# Sheet1.net
KiCad netlist of a schematic drawn in Altium Designer
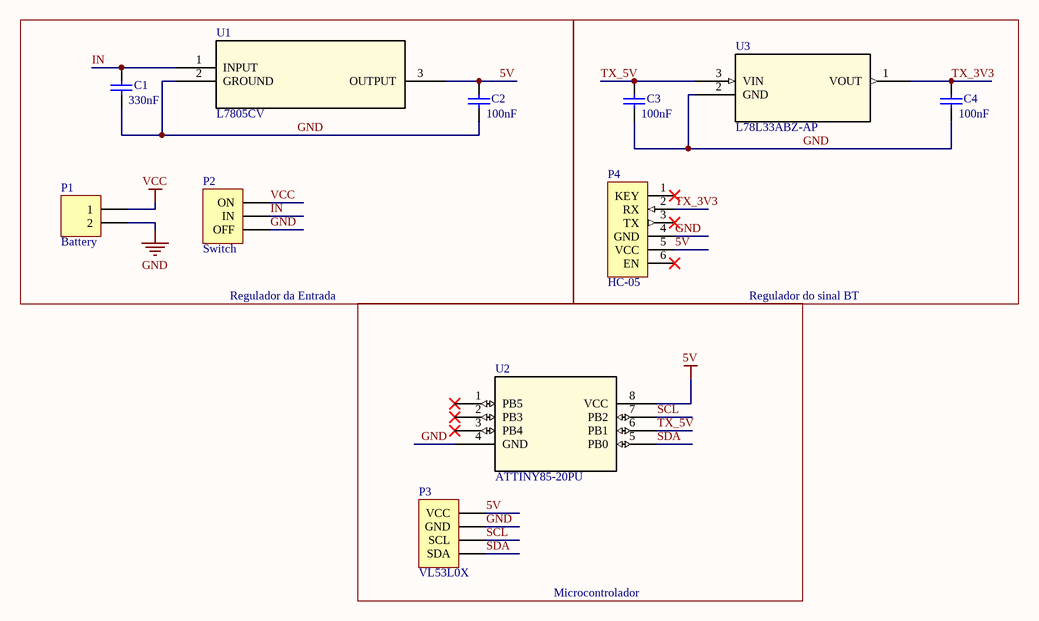
[diagram p0: Sheet1.SchDoc]

(export (version "E")
  (design (tool "Eeschema 10.0.6"))
  (components
    (comp (ref "C1")
      (value "330nF")
      (footprint "RAD-0.3")
      (description "Capacitor")
      (fields (field (name "Comment") "Cap") (field (name "PUBLISHER") "Altium Limited"))
      (libsource (lib "Miscellaneous Devices") (part "Cap"))
    )
    (comp (ref "C2")
      (value "100nF")
      (footprint "RAD-0.3")
      (description "Capacitor")
      (fields (field (name "Comment") "Cap") (field (name "PUBLISHER") "Altium Limited"))
      (libsource (lib "Miscellaneous Devices") (part "Cap"))
    )
    (comp (ref "C3")
      (value "100nF")
      (footprint "RAD-0.2")
      (description "Capacitor")
      (libsource (lib "Basic Library") (part "C"))
    )
    (comp (ref "C4")
      (value "100nF")
      (footprint "RAD-0.2")
      (description "Capacitor")
      (libsource (lib "Basic Library") (part "C"))
    )
    (comp (ref "P1")
      (value "Battery")
      (footprint "HDR1X2")
      (description "Header, 2-Pin")
      (fields (field (name "PUBLISHER") "Altium Limited"))
      (libsource (lib "Miscellaneous Connectors") (part "Header 2"))
    )
    (comp (ref "P2")
      (value "Switch")
      (footprint "HDR1X3")
      (description "Header, 3-Pin")
      (fields (field (name "PUBLISHER") "Altium Limited"))
      (libsource (lib "Miscellaneous Connectors") (part "Header 3"))
    )
    (comp (ref "P3")
      (value "VL53L0X")
      (footprint "HDR1X4")
      (description "Header, 4-Pin")
      (fields (field (name "PUBLISHER") "Altium Limited"))
      (libsource (lib "Miscellaneous Connectors") (part "Header 4"))
    )
    (comp (ref "P4")
      (value "HC-05")
      (footprint "HDR1X6")
      (description "Header, 6-Pin")
      (fields (field (name "PUBLISHER") "Altium Limited"))
      (libsource (lib "Miscellaneous Connectors") (part "Header 6"))
    )
    (comp (ref "U1")
      (value "L7805CV")
      (footprint "TO-220_STM")
      (description "No Description Available")
      (fields (field (name "COPYRIGHT") "Copyright (C) 2021 Ultra Librarian. All rights reserved."))
      (libsource (lib "L7805CV") (part "L7805CV"))
    )
    (comp (ref "U2")
      (value "ATTINY85-20PU")
      (footprint "8P3_ATM")
      (description "No Description Available")
      (fields (field (name "COPYRIGHT") "Copyright (C) 2021 Ultra Librarian. All rights reserved."))
      (libsource (lib "ATTINY85-20PU") (part "ATTINY85-20PU"))
    )
    (comp (ref "U3")
      (value "L78L33ABZ-AP")
      (footprint "TO-92-TR_STM")
      (description "No Description Available")
      (fields (field (name "COPYRIGHT") "Copyright (C) 2021 Ultra Librarian. All rights reserved."))
      (libsource (lib "L78L33ABZ-AP") (part "L78L33ABZ-AP"))
    )
  )
  (nets
    (net (code "1") (name "/IN") (class "Default")
      (node (ref "C1") (pin "2") (pinfunction "2_2") (pintype "passive"))
      (node (ref "P2") (pin "2") (pinfunction "IN_2") (pintype "passive"))
      (node (ref "U1") (pin "1") (pinfunction "INPUT_1") (pintype "passive"))
    )
    (net (code "2") (name "/SCL") (class "Default")
      (node (ref "P3") (pin "3") (pinfunction "SCL_3") (pintype "passive"))
      (node (ref "U2") (pin "7") (pinfunction "PB2_7") (pintype "bidirectional"))
    )
    (net (code "3") (name "/SDA") (class "Default")
      (node (ref "P3") (pin "4") (pinfunction "SDA_4") (pintype "passive"))
      (node (ref "U2") (pin "5") (pinfunction "PB0_5") (pintype "bidirectional"))
    )
    (net (code "4") (name "/TX_3V3") (class "Default")
      (node (ref "C4") (pin "2") (pinfunction "2_2") (pintype "passive"))
      (node (ref "P4") (pin "2") (pinfunction "RX_2") (pintype "input"))
      (node (ref "U3") (pin "1") (pinfunction "VOUT_1") (pintype "output"))
    )
    (net (code "5") (name "/TX_5V") (class "Default")
      (node (ref "C3") (pin "2") (pinfunction "2_2") (pintype "passive"))
      (node (ref "U2") (pin "6") (pinfunction "PB1_6") (pintype "bidirectional"))
      (node (ref "U3") (pin "3") (pinfunction "VIN_3") (pintype "input"))
    )
    (net (code "6") (name "5V") (class "Default")
      (node (ref "C2") (pin "2") (pinfunction "2_2") (pintype "passive"))
      (node (ref "P3") (pin "1") (pinfunction "VCC_1") (pintype "passive"))
      (node (ref "P4") (pin "5") (pinfunction "VCC_5") (pintype "passive"))
      (node (ref "U1") (pin "3") (pinfunction "OUTPUT_3") (pintype "passive"))
      (node (ref "U2") (pin "8") (pinfunction "VCC_8") (pintype "power_in"))
    )
    (net (code "7") (name "GND") (class "Default")
      (node (ref "C1") (pin "1") (pinfunction "1_1") (pintype "passive"))
      (node (ref "C2") (pin "1") (pinfunction "1_1") (pintype "passive"))
      (node (ref "C3") (pin "1") (pinfunction "1_1") (pintype "passive"))
      (node (ref "C4") (pin "1") (pinfunction "1_1") (pintype "passive"))
      (node (ref "P1") (pin "2") (pinfunction "2_2") (pintype "passive"))
      (node (ref "P2") (pin "3") (pinfunction "OFF_3") (pintype "passive"))
      (node (ref "P3") (pin "2") (pinfunction "GND_2") (pintype "passive"))
      (node (ref "P4") (pin "4") (pinfunction "GND_4") (pintype "passive"))
      (node (ref "U1") (pin "2") (pinfunction "GROUND_2") (pintype "passive"))
      (node (ref "U2") (pin "4") (pinfunction "GND_4") (pintype "power_in"))
      (node (ref "U3") (pin "2") (pinfunction "GND_2") (pintype "passive"))
    )
    (net (code "8") (name "VCC") (class "Default")
      (node (ref "P1") (pin "1") (pinfunction "1_1") (pintype "passive"))
      (node (ref "P2") (pin "1") (pinfunction "ON_1") (pintype "passive"))
    )
    (net (code "9") (name "unconnected-(P4-EN-Pad6)") (class "Default")
      (node (ref "P4") (pin "6") (pinfunction "EN_6") (pintype "passive+no_connect"))
    )
    (net (code "10") (name "unconnected-(P4-KEY-Pad1)") (class "Default")
      (node (ref "P4") (pin "1") (pinfunction "KEY_1") (pintype "passive+no_connect"))
    )
    (net (code "11") (name "unconnected-(P4-TX-Pad3)") (class "Default")
      (node (ref "P4") (pin "3") (pinfunction "TX_3") (pintype "output+no_connect"))
    )
    (net (code "12") (name "unconnected-(U2-PB3-Pad2)") (class "Default")
      (node (ref "U2") (pin "2") (pinfunction "PB3_2") (pintype "bidirectional+no_connect"))
    )
    (net (code "13") (name "unconnected-(U2-PB4-Pad3)") (class "Default")
      (node (ref "U2") (pin "3") (pinfunction "PB4_3") (pintype "bidirectional+no_connect"))
    )
    (net (code "14") (name "unconnected-(U2-PB5-Pad1)") (class "Default")
      (node (ref "U2") (pin "1") (pinfunction "PB5_1") (pintype "bidirectional+no_connect"))
    )
  )
)
